# ChessMate.net
KiCad netlist of a schematic drawn in EAGLE
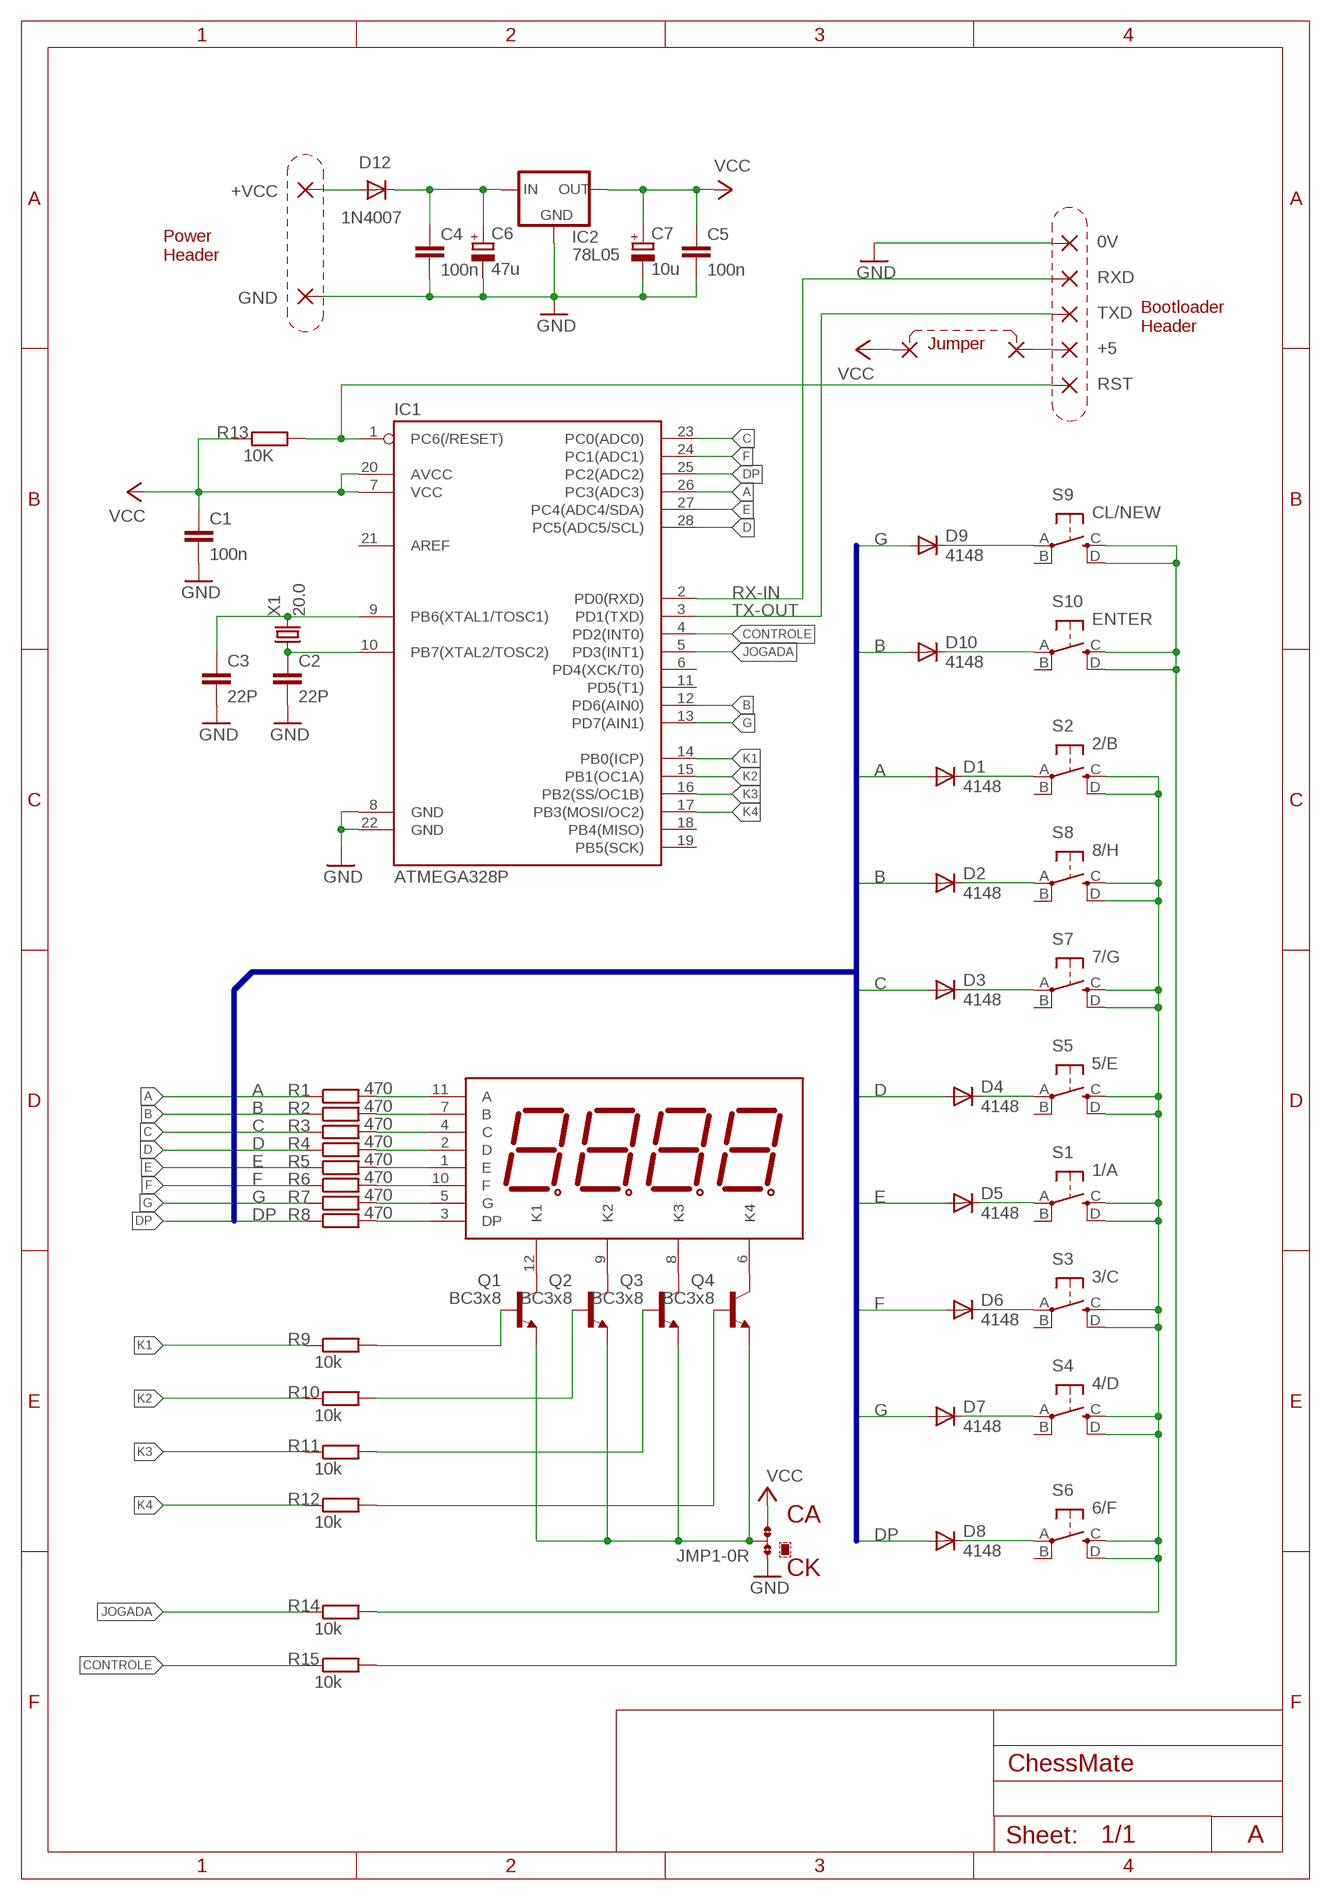
[diagram p0: schematic, sheet 1]

(export (version "E")
  (design (tool "Eeschema 10.0.6"))
  (components
    (comp (ref "+5")
      (value "2,15/1,0")
      (footprint "eagle-import:2,15_1,0")
      (libsource (lib "eagle-import") (part "2,15/1,0"))
    )
    (comp (ref "+VCC")
      (value "2,15/1,0")
      (footprint "eagle-import:2,15_1,0")
      (libsource (lib "eagle-import") (part "2,15/1,0"))
    )
    (comp (ref "0V")
      (value "2,15/1,0")
      (footprint "eagle-import:2,15_1,0")
      (libsource (lib "eagle-import") (part "2,15/1,0"))
    )
    (comp (ref "C1")
      (value "100n")
      (footprint "eagle-import:C050-024X044L")
      (libsource (lib "eagle-import") (part "C-EUC050-024X044L"))
    )
    (comp (ref "C2")
      (value "22P")
      (footprint "eagle-import:C025-024X044L")
      (libsource (lib "eagle-import") (part "C-EU"))
    )
    (comp (ref "C3")
      (value "22P")
      (footprint "eagle-import:C025-024X044L")
      (libsource (lib "eagle-import") (part "C-EU"))
    )
    (comp (ref "C4")
      (value "100n")
      (footprint "eagle-import:C050-024X044L")
      (libsource (lib "eagle-import") (part "C-EUC050-024X044L"))
    )
    (comp (ref "C5")
      (value "100n")
      (footprint "eagle-import:C050-024X044L")
      (libsource (lib "eagle-import") (part "C-EUC050-024X044L"))
    )
    (comp (ref "C6")
      (value "47u")
      (footprint "eagle-import:TT2D7L")
      (libsource (lib "eagle-import") (part "CPOL-EUTT2D7L"))
    )
    (comp (ref "C7")
      (value "10u")
      (footprint "eagle-import:TT2D7L")
      (libsource (lib "eagle-import") (part "CPOL-EUTT2D7L"))
    )
    (comp (ref "D1")
      (value "4148")
      (footprint "eagle-import:DO35-7")
      (libsource (lib "eagle-import") (part "1N4148DO35-7"))
    )
    (comp (ref "D2")
      (value "4148")
      (footprint "eagle-import:DO35-7")
      (libsource (lib "eagle-import") (part "1N4148DO35-7"))
    )
    (comp (ref "D3")
      (value "4148")
      (footprint "eagle-import:DO35-7")
      (libsource (lib "eagle-import") (part "1N4148DO35-7"))
    )
    (comp (ref "D4")
      (value "4148")
      (footprint "eagle-import:DO35-7")
      (libsource (lib "eagle-import") (part "1N4148DO35-7"))
    )
    (comp (ref "D5")
      (value "4148")
      (footprint "eagle-import:DO35-7")
      (libsource (lib "eagle-import") (part "1N4148DO35-7"))
    )
    (comp (ref "D6")
      (value "4148")
      (footprint "eagle-import:DO35-7")
      (libsource (lib "eagle-import") (part "1N4148DO35-7"))
    )
    (comp (ref "D7")
      (value "4148")
      (footprint "eagle-import:DO35-7")
      (libsource (lib "eagle-import") (part "1N4148DO35-7"))
    )
    (comp (ref "D8")
      (value "4148")
      (footprint "eagle-import:DO35-7")
      (libsource (lib "eagle-import") (part "1N4148DO35-7"))
    )
    (comp (ref "D9")
      (value "4148")
      (footprint "eagle-import:DO35-7")
      (libsource (lib "eagle-import") (part "1N4148DO35-7"))
    )
    (comp (ref "D10")
      (value "4148")
      (footprint "eagle-import:DO35-7")
      (libsource (lib "eagle-import") (part "1N4148DO35-7"))
    )
    (comp (ref "D12")
      (value "1N4007")
      (footprint "eagle-import:DO41-7.6L")
      (libsource (lib "eagle-import") (part "DIODE-DO41-7.7L"))
    )
    (comp (ref "GND")
      (value "2,15/1,0")
      (footprint "eagle-import:2,15_1,0")
      (libsource (lib "eagle-import") (part "2,15/1,0"))
    )
    (comp (ref "IC1")
      (value "ATMEGA328P")
      (footprint "eagle-import:DIL28-3")
      (libsource (lib "eagle-import") (part "ATMEGA328P_PDIP"))
    )
    (comp (ref "IC2")
      (value "78L05")
      (footprint "eagle-import:TO92_")
      (libsource (lib "eagle-import") (part "78LXXTO92_"))
    )
    (comp (ref "JMP1")
      (value "0R-JUMPA")
      (footprint "eagle-import:A0R-JMP")
      (libsource (lib "eagle-import") (part "0R-JUMPA"))
    )
    (comp (ref "LD1")
      (value "4_DIGIT-TOF3461BH-N")
      (footprint "eagle-import:TOF3461BH-N")
      (libsource (lib "eagle-import") (part "4_DIGIT-TOF3461BH-N"))
    )
    (comp (ref "PAD1")
      (value "1,6/0,8")
      (footprint "eagle-import:1,6_0,8")
      (libsource (lib "eagle-import") (part "1,6/0,8"))
    )
    (comp (ref "PAD2")
      (value "1,6/0,8")
      (footprint "eagle-import:1,6_0,8")
      (libsource (lib "eagle-import") (part "1,6/0,8"))
    )
    (comp (ref "Q1")
      (value "BC3x8")
      (footprint "eagle-import:TO92-EBC")
      (libsource (lib "eagle-import") (part "BC338"))
    )
    (comp (ref "Q2")
      (value "BC3x8")
      (footprint "eagle-import:TO92-EBC")
      (libsource (lib "eagle-import") (part "BC338"))
    )
    (comp (ref "Q3")
      (value "BC3x8")
      (footprint "eagle-import:TO92-EBC")
      (libsource (lib "eagle-import") (part "BC338"))
    )
    (comp (ref "Q4")
      (value "BC3x8")
      (footprint "eagle-import:TO92-EBC")
      (libsource (lib "eagle-import") (part "BC338"))
    )
    (comp (ref "R1")
      (value "470")
      (footprint "eagle-import:0204_7L")
      (libsource (lib "eagle-import") (part "R-EU_0204/7L"))
    )
    (comp (ref "R2")
      (value "470")
      (footprint "eagle-import:0204_7L")
      (libsource (lib "eagle-import") (part "R-EU_0204/7L"))
    )
    (comp (ref "R3")
      (value "470")
      (footprint "eagle-import:0204_7L")
      (libsource (lib "eagle-import") (part "R-EU_0204/7L"))
    )
    (comp (ref "R4")
      (value "470")
      (footprint "eagle-import:0204_7L")
      (libsource (lib "eagle-import") (part "R-EU_0204/7L"))
    )
    (comp (ref "R5")
      (value "470")
      (footprint "eagle-import:0204_7L")
      (libsource (lib "eagle-import") (part "R-EU_0204/7L"))
    )
    (comp (ref "R6")
      (value "470")
      (footprint "eagle-import:0204_7L")
      (libsource (lib "eagle-import") (part "R-EU_0204/7L"))
    )
    (comp (ref "R7")
      (value "470")
      (footprint "eagle-import:0204_7L")
      (libsource (lib "eagle-import") (part "R-EU_0204/7L"))
    )
    (comp (ref "R8")
      (value "470")
      (footprint "eagle-import:0204_7L")
      (libsource (lib "eagle-import") (part "R-EU_0204/7L"))
    )
    (comp (ref "R9")
      (value "10k")
      (footprint "eagle-import:0204_7L")
      (libsource (lib "eagle-import") (part "R-EU_0204/7L"))
    )
    (comp (ref "R10")
      (value "10k")
      (footprint "eagle-import:0204_7L")
      (libsource (lib "eagle-import") (part "R-EU_0204/7L"))
    )
    (comp (ref "R11")
      (value "10k")
      (footprint "eagle-import:0204_7L")
      (libsource (lib "eagle-import") (part "R-EU_0204/7L"))
    )
    (comp (ref "R12")
      (value "10k")
      (footprint "eagle-import:0204_7L")
      (libsource (lib "eagle-import") (part "R-EU_0204/7L"))
    )
    (comp (ref "R13")
      (value "10K")
      (footprint "eagle-import:0204_5L")
      (libsource (lib "eagle-import") (part "R-EU_0204/5L"))
    )
    (comp (ref "R14")
      (value "10k")
      (footprint "eagle-import:0204_7L")
      (libsource (lib "eagle-import") (part "R-EU_0204/7L"))
    )
    (comp (ref "R15")
      (value "10k")
      (footprint "eagle-import:0204_7L")
      (libsource (lib "eagle-import") (part "R-EU_0204/7L"))
    )
    (comp (ref "RST")
      (value "2,15/1,0")
      (footprint "eagle-import:2,15_1,0")
      (libsource (lib "eagle-import") (part "2,15/1,0"))
    )
    (comp (ref "RXD")
      (value "2,15/1,0")
      (footprint "eagle-import:2,15_1,0")
      (libsource (lib "eagle-import") (part "2,15/1,0"))
    )
    (comp (ref "S1")
      (value "1/A")
      (footprint "eagle-import:TACT_SW")
      (libsource (lib "eagle-import") (part "10-XXTACT"))
    )
    (comp (ref "S2")
      (value "2/B")
      (footprint "eagle-import:TACT_SW")
      (libsource (lib "eagle-import") (part "10-XXTACT"))
    )
    (comp (ref "S3")
      (value "3/C")
      (footprint "eagle-import:TACT_SW")
      (libsource (lib "eagle-import") (part "10-XXTACT"))
    )
    (comp (ref "S4")
      (value "4/D")
      (footprint "eagle-import:TACT_SW")
      (libsource (lib "eagle-import") (part "10-XXTACT"))
    )
    (comp (ref "S5")
      (value "5/E")
      (footprint "eagle-import:TACT_SW")
      (libsource (lib "eagle-import") (part "10-XXTACT"))
    )
    (comp (ref "S6")
      (value "6/F")
      (footprint "eagle-import:TACT_SW")
      (libsource (lib "eagle-import") (part "10-XXTACT"))
    )
    (comp (ref "S7")
      (value "7/G")
      (footprint "eagle-import:TACT_SW")
      (libsource (lib "eagle-import") (part "10-XXTACT"))
    )
    (comp (ref "S8")
      (value "8/H")
      (footprint "eagle-import:TACT_SW")
      (libsource (lib "eagle-import") (part "10-XXTACT"))
    )
    (comp (ref "S9")
      (value "CL/NEW")
      (footprint "eagle-import:TACT_SW")
      (libsource (lib "eagle-import") (part "10-XXTACT"))
    )
    (comp (ref "S10")
      (value "ENTER")
      (footprint "eagle-import:TACT_SW")
      (libsource (lib "eagle-import") (part "10-XXTACT"))
    )
    (comp (ref "TXD")
      (value "2,15/1,0")
      (footprint "eagle-import:2,15_1,0")
      (libsource (lib "eagle-import") (part "2,15/1,0"))
    )
    (comp (ref "X1")
      (value "20.0")
      (footprint "eagle-import:HC49_SL")
      (libsource (lib "eagle-import") (part "CRYSTALHC49/SL"))
    )
  )
  (nets
    (net (code "1") (name "/RX-IN") (class "Default")
      (node (ref "IC1") (pin "2") (pinfunction "PD0(RXD)_2") (pintype "bidirectional"))
      (node (ref "RXD") (pin "1") (pinfunction "P_1") (pintype "passive"))
    )
    (net (code "2") (name "/TX-OUT") (class "Default")
      (node (ref "IC1") (pin "3") (pinfunction "PD1(TXD)_3") (pintype "bidirectional"))
      (node (ref "TXD") (pin "1") (pinfunction "P_1") (pintype "passive"))
    )
    (net (code "3") (name "A") (class "Default")
      (node (ref "D1") (pin "A") (pinfunction "A_A") (pintype "passive"))
      (node (ref "IC1") (pin "26") (pinfunction "PC3(ADC3)_26") (pintype "bidirectional"))
      (node (ref "R1") (pin "1") (pinfunction "1_1") (pintype "passive"))
    )
    (net (code "4") (name "B") (class "Default")
      (node (ref "D10") (pin "A") (pinfunction "A_A") (pintype "passive"))
      (node (ref "D2") (pin "A") (pinfunction "A_A") (pintype "passive"))
      (node (ref "IC1") (pin "12") (pinfunction "PD6(AIN0)_12") (pintype "bidirectional"))
      (node (ref "R2") (pin "1") (pinfunction "1_1") (pintype "passive"))
    )
    (net (code "5") (name "C") (class "Default")
      (node (ref "D3") (pin "A") (pinfunction "A_A") (pintype "passive"))
      (node (ref "IC1") (pin "23") (pinfunction "PC0(ADC0)_23") (pintype "bidirectional"))
      (node (ref "R3") (pin "1") (pinfunction "1_1") (pintype "passive"))
    )
    (net (code "6") (name "CONTROLE") (class "Default")
      (node (ref "IC1") (pin "4") (pinfunction "PD2(INT0)_4") (pintype "bidirectional"))
      (node (ref "R15") (pin "1") (pinfunction "1_1") (pintype "passive"))
    )
    (net (code "7") (name "D") (class "Default")
      (node (ref "D4") (pin "A") (pinfunction "A_A") (pintype "passive"))
      (node (ref "IC1") (pin "28") (pinfunction "PC5(ADC5/SCL)_28") (pintype "bidirectional"))
      (node (ref "R4") (pin "1") (pinfunction "1_1") (pintype "passive"))
    )
    (net (code "8") (name "DP") (class "Default")
      (node (ref "D8") (pin "A") (pinfunction "A_A") (pintype "passive"))
      (node (ref "IC1") (pin "25") (pinfunction "PC2(ADC2)_25") (pintype "bidirectional"))
      (node (ref "R8") (pin "1") (pinfunction "1_1") (pintype "passive"))
    )
    (net (code "9") (name "E") (class "Default")
      (node (ref "D5") (pin "A") (pinfunction "A_A") (pintype "passive"))
      (node (ref "IC1") (pin "27") (pinfunction "PC4(ADC4/SDA)_27") (pintype "bidirectional"))
      (node (ref "R5") (pin "1") (pinfunction "1_1") (pintype "passive"))
    )
    (net (code "10") (name "F") (class "Default")
      (node (ref "D6") (pin "A") (pinfunction "A_A") (pintype "passive"))
      (node (ref "IC1") (pin "24") (pinfunction "PC1(ADC1)_24") (pintype "bidirectional"))
      (node (ref "R6") (pin "1") (pinfunction "1_1") (pintype "passive"))
    )
    (net (code "11") (name "G") (class "Default")
      (node (ref "D7") (pin "A") (pinfunction "A_A") (pintype "passive"))
      (node (ref "D9") (pin "A") (pinfunction "A_A") (pintype "passive"))
      (node (ref "IC1") (pin "13") (pinfunction "PD7(AIN1)_13") (pintype "bidirectional"))
      (node (ref "R7") (pin "1") (pinfunction "1_1") (pintype "passive"))
    )
    (net (code "12") (name "GND") (class "Default")
      (node (ref "0V") (pin "1") (pinfunction "P_1") (pintype "passive"))
      (node (ref "C1") (pin "2") (pinfunction "2_2") (pintype "passive"))
      (node (ref "C2") (pin "2") (pinfunction "2_2") (pintype "passive"))
      (node (ref "C3") (pin "2") (pinfunction "2_2") (pintype "passive"))
      (node (ref "C4") (pin "2") (pinfunction "2_2") (pintype "passive"))
      (node (ref "C5") (pin "2") (pinfunction "2_2") (pintype "passive"))
      (node (ref "C6") (pin "-") (pinfunction "-_-") (pintype "passive"))
      (node (ref "C7") (pin "-") (pinfunction "-_-") (pintype "passive"))
      (node (ref "GND") (pin "1") (pinfunction "P_1") (pintype "passive"))
      (node (ref "IC1") (pin "22") (pinfunction "GND_22") (pintype "bidirectional"))
      (node (ref "IC1") (pin "8") (pinfunction "GND_8") (pintype "bidirectional"))
      (node (ref "IC2") (pin "2") (pinfunction "GND_2") (pintype "input"))
      (node (ref "JMP1") (pin "1") (pinfunction "1_1") (pintype "passive"))
    )
    (net (code "13") (name "JOGADA") (class "Default")
      (node (ref "IC1") (pin "5") (pinfunction "PD3(INT1)_5") (pintype "bidirectional"))
      (node (ref "R14") (pin "1") (pinfunction "1_1") (pintype "passive"))
    )
    (net (code "14") (name "K1") (class "Default")
      (node (ref "IC1") (pin "14") (pinfunction "PB0(ICP)_14") (pintype "bidirectional"))
      (node (ref "R9") (pin "1") (pinfunction "1_1") (pintype "passive"))
    )
    (net (code "15") (name "K2") (class "Default")
      (node (ref "IC1") (pin "15") (pinfunction "PB1(OC1A)_15") (pintype "bidirectional"))
      (node (ref "R10") (pin "1") (pinfunction "1_1") (pintype "passive"))
    )
    (net (code "16") (name "K3") (class "Default")
      (node (ref "IC1") (pin "16") (pinfunction "PB2(SS/OC1B)_16") (pintype "bidirectional"))
      (node (ref "R11") (pin "1") (pinfunction "1_1") (pintype "passive"))
    )
    (net (code "17") (name "K4") (class "Default")
      (node (ref "IC1") (pin "17") (pinfunction "PB3(MOSI/OC2)_17") (pintype "bidirectional"))
      (node (ref "R12") (pin "1") (pinfunction "1_1") (pintype "passive"))
    )
    (net (code "18") (name "Net-(+5-P)") (class "Default")
      (node (ref "+5") (pin "1") (pinfunction "P_1") (pintype "passive"))
      (node (ref "PAD2") (pin "1") (pinfunction "P_1") (pintype "passive"))
    )
    (net (code "19") (name "Net-(+VCC-P)") (class "Default")
      (node (ref "+VCC") (pin "1") (pinfunction "P_1") (pintype "passive"))
      (node (ref "D12") (pin "A") (pinfunction "A_A") (pintype "passive"))
    )
    (net (code "20") (name "Net-(IC1-PB6(XTAL1{slash}TOSC1))") (class "Default")
      (node (ref "C3") (pin "1") (pinfunction "1_1") (pintype "passive"))
      (node (ref "IC1") (pin "9") (pinfunction "PB6(XTAL1/TOSC1)_9") (pintype "bidirectional"))
      (node (ref "X1") (pin "2") (pinfunction "2_2") (pintype "passive"))
    )
    (net (code "21") (name "Net-(IC1-PB7(XTAL2{slash}TOSC2))") (class "Default")
      (node (ref "C2") (pin "1") (pinfunction "1_1") (pintype "passive"))
      (node (ref "IC1") (pin "10") (pinfunction "PB7(XTAL2/TOSC2)_10") (pintype "bidirectional"))
      (node (ref "X1") (pin "1") (pinfunction "1_1") (pintype "passive"))
    )
    (net (code "22") (name "Net-(IC1-PC6({slash}RESET))") (class "Default")
      (node (ref "IC1") (pin "1") (pinfunction "PC6(/RESET)_1") (pintype "bidirectional"))
      (node (ref "R13") (pin "2") (pinfunction "2_2") (pintype "passive"))
      (node (ref "RST") (pin "1") (pinfunction "P_1") (pintype "passive"))
    )
    (net (code "23") (name "Net-(IC2-IN)") (class "Default")
      (node (ref "C4") (pin "1") (pinfunction "1_1") (pintype "passive"))
      (node (ref "C6") (pin "+") (pinfunction "+_+") (pintype "passive"))
      (node (ref "D12") (pin "C") (pinfunction "C_C") (pintype "passive"))
      (node (ref "IC2") (pin "3") (pinfunction "IN_3") (pintype "input"))
    )
    (net (code "24") (name "Net-(JMP1-Pad2)") (class "Default")
      (node (ref "JMP1") (pin "2") (pinfunction "2_2") (pintype "passive"))
      (node (ref "Q1") (pin "E") (pinfunction "E_E") (pintype "passive"))
      (node (ref "Q2") (pin "E") (pinfunction "E_E") (pintype "passive"))
      (node (ref "Q3") (pin "E") (pinfunction "E_E") (pintype "passive"))
      (node (ref "Q4") (pin "E") (pinfunction "E_E") (pintype "passive"))
    )
    (net (code "25") (name "Net-(LD1-A)") (class "Default")
      (node (ref "LD1") (pin "11") (pinfunction "A_11") (pintype "input"))
      (node (ref "R1") (pin "2") (pinfunction "2_2") (pintype "passive"))
    )
    (net (code "26") (name "Net-(LD1-B)") (class "Default")
      (node (ref "LD1") (pin "7") (pinfunction "B_7") (pintype "input"))
      (node (ref "R2") (pin "2") (pinfunction "2_2") (pintype "passive"))
    )
    (net (code "27") (name "Net-(LD1-C)") (class "Default")
      (node (ref "LD1") (pin "4") (pinfunction "C_4") (pintype "input"))
      (node (ref "R3") (pin "2") (pinfunction "2_2") (pintype "passive"))
    )
    (net (code "28") (name "Net-(LD1-D)") (class "Default")
      (node (ref "LD1") (pin "2") (pinfunction "D_2") (pintype "input"))
      (node (ref "R4") (pin "2") (pinfunction "2_2") (pintype "passive"))
    )
    (net (code "29") (name "Net-(LD1-DP)") (class "Default")
      (node (ref "LD1") (pin "3") (pinfunction "DP_3") (pintype "input"))
      (node (ref "R8") (pin "2") (pinfunction "2_2") (pintype "passive"))
    )
    (net (code "30") (name "Net-(LD1-E)") (class "Default")
      (node (ref "LD1") (pin "1") (pinfunction "E_1") (pintype "input"))
      (node (ref "R5") (pin "2") (pinfunction "2_2") (pintype "passive"))
    )
    (net (code "31") (name "Net-(LD1-F)") (class "Default")
      (node (ref "LD1") (pin "10") (pinfunction "F_10") (pintype "input"))
      (node (ref "R6") (pin "2") (pinfunction "2_2") (pintype "passive"))
    )
    (net (code "32") (name "Net-(LD1-G)") (class "Default")
      (node (ref "LD1") (pin "5") (pinfunction "G_5") (pintype "input"))
      (node (ref "R7") (pin "2") (pinfunction "2_2") (pintype "passive"))
    )
    (net (code "33") (name "Net-(LD1-K1)") (class "Default")
      (node (ref "LD1") (pin "12") (pinfunction "K1_12") (pintype "input"))
      (node (ref "Q1") (pin "C") (pinfunction "C_C") (pintype "passive"))
    )
    (net (code "34") (name "Net-(LD1-K2)") (class "Default")
      (node (ref "LD1") (pin "9") (pinfunction "K2_9") (pintype "input"))
      (node (ref "Q2") (pin "C") (pinfunction "C_C") (pintype "passive"))
    )
    (net (code "35") (name "Net-(LD1-K3)") (class "Default")
      (node (ref "LD1") (pin "8") (pinfunction "K3_8") (pintype "input"))
      (node (ref "Q3") (pin "C") (pinfunction "C_C") (pintype "passive"))
    )
    (net (code "36") (name "Net-(LD1-K4)") (class "Default")
      (node (ref "LD1") (pin "6") (pinfunction "K4_6") (pintype "input"))
      (node (ref "Q4") (pin "C") (pinfunction "C_C") (pintype "passive"))
    )
    (net (code "37") (name "Net-(Q1-PadB)") (class "Default")
      (node (ref "Q1") (pin "B") (pinfunction "B_B") (pintype "passive"))
      (node (ref "R9") (pin "2") (pinfunction "2_2") (pintype "passive"))
    )
    (net (code "38") (name "Net-(Q2-PadB)") (class "Default")
      (node (ref "Q2") (pin "B") (pinfunction "B_B") (pintype "passive"))
      (node (ref "R10") (pin "2") (pinfunction "2_2") (pintype "passive"))
    )
    (net (code "39") (name "Net-(Q3-PadB)") (class "Default")
      (node (ref "Q3") (pin "B") (pinfunction "B_B") (pintype "passive"))
      (node (ref "R11") (pin "2") (pinfunction "2_2") (pintype "passive"))
    )
    (net (code "40") (name "Net-(Q4-PadB)") (class "Default")
      (node (ref "Q4") (pin "B") (pinfunction "B_B") (pintype "passive"))
      (node (ref "R12") (pin "2") (pinfunction "2_2") (pintype "passive"))
    )
    (net (code "41") (name "Net-(S1-P)") (class "Default")
      (node (ref "D5") (pin "C") (pinfunction "C_C") (pintype "passive"))
      (node (ref "S1") (pin "A") (pinfunction "P_A") (pintype "passive"))
    )
    (net (code "42") (name "Net-(S1-S)") (class "Default")
      (node (ref "R14") (pin "2") (pinfunction "2_2") (pintype "passive"))
      (node (ref "S1") (pin "C") (pinfunction "S_C") (pintype "passive"))
      (node (ref "S1") (pin "D") (pinfunction "S1_D") (pintype "passive"))
      (node (ref "S2") (pin "C") (pinfunction "S_C") (pintype "passive"))
      (node (ref "S2") (pin "D") (pinfunction "S1_D") (pintype "passive"))
      (node (ref "S3") (pin "C") (pinfunction "S_C") (pintype "passive"))
      (node (ref "S3") (pin "D") (pinfunction "S1_D") (pintype "passive"))
      (node (ref "S4") (pin "C") (pinfunction "S_C") (pintype "passive"))
      (node (ref "S4") (pin "D") (pinfunction "S1_D") (pintype "passive"))
      (node (ref "S5") (pin "C") (pinfunction "S_C") (pintype "passive"))
      (node (ref "S5") (pin "D") (pinfunction "S1_D") (pintype "passive"))
      (node (ref "S6") (pin "C") (pinfunction "S_C") (pintype "passive"))
      (node (ref "S6") (pin "D") (pinfunction "S1_D") (pintype "passive"))
      (node (ref "S7") (pin "C") (pinfunction "S_C") (pintype "passive"))
      (node (ref "S7") (pin "D") (pinfunction "S1_D") (pintype "passive"))
      (node (ref "S8") (pin "C") (pinfunction "S_C") (pintype "passive"))
      (node (ref "S8") (pin "D") (pinfunction "S1_D") (pintype "passive"))
    )
    (net (code "43") (name "Net-(S2-P)") (class "Default")
      (node (ref "D1") (pin "C") (pinfunction "C_C") (pintype "passive"))
      (node (ref "S2") (pin "A") (pinfunction "P_A") (pintype "passive"))
    )
    (net (code "44") (name "Net-(S3-P)") (class "Default")
      (node (ref "D6") (pin "C") (pinfunction "C_C") (pintype "passive"))
      (node (ref "S3") (pin "A") (pinfunction "P_A") (pintype "passive"))
    )
    (net (code "45") (name "Net-(S4-P)") (class "Default")
      (node (ref "D7") (pin "C") (pinfunction "C_C") (pintype "passive"))
      (node (ref "S4") (pin "A") (pinfunction "P_A") (pintype "passive"))
    )
    (net (code "46") (name "Net-(S5-P)") (class "Default")
      (node (ref "D4") (pin "C") (pinfunction "C_C") (pintype "passive"))
      (node (ref "S5") (pin "A") (pinfunction "P_A") (pintype "passive"))
    )
    (net (code "47") (name "Net-(S6-P)") (class "Default")
      (node (ref "D8") (pin "C") (pinfunction "C_C") (pintype "passive"))
      (node (ref "S6") (pin "A") (pinfunction "P_A") (pintype "passive"))
    )
    (net (code "48") (name "Net-(S7-P)") (class "Default")
      (node (ref "D3") (pin "C") (pinfunction "C_C") (pintype "passive"))
      (node (ref "S7") (pin "A") (pinfunction "P_A") (pintype "passive"))
    )
    (net (code "49") (name "Net-(S8-P)") (class "Default")
      (node (ref "D2") (pin "C") (pinfunction "C_C") (pintype "passive"))
      (node (ref "S8") (pin "A") (pinfunction "P_A") (pintype "passive"))
    )
    (net (code "50") (name "Net-(S9-P)") (class "Default")
      (node (ref "D9") (pin "C") (pinfunction "C_C") (pintype "passive"))
      (node (ref "S9") (pin "A") (pinfunction "P_A") (pintype "passive"))
    )
    (net (code "51") (name "Net-(S10-P)") (class "Default")
      (node (ref "D10") (pin "C") (pinfunction "C_C") (pintype "passive"))
      (node (ref "S10") (pin "A") (pinfunction "P_A") (pintype "passive"))
    )
    (net (code "52") (name "Net-(S10-S)") (class "Default")
      (node (ref "R15") (pin "2") (pinfunction "2_2") (pintype "passive"))
      (node (ref "S10") (pin "C") (pinfunction "S_C") (pintype "passive"))
      (node (ref "S10") (pin "D") (pinfunction "S1_D") (pintype "passive"))
      (node (ref "S9") (pin "C") (pinfunction "S_C") (pintype "passive"))
      (node (ref "S9") (pin "D") (pinfunction "S1_D") (pintype "passive"))
    )
    (net (code "53") (name "VCC") (class "Default")
      (node (ref "C1") (pin "1") (pinfunction "1_1") (pintype "passive"))
      (node (ref "C5") (pin "1") (pinfunction "1_1") (pintype "passive"))
      (node (ref "C7") (pin "+") (pinfunction "+_+") (pintype "passive"))
      (node (ref "IC1") (pin "20") (pinfunction "AVCC_20") (pintype "bidirectional"))
      (node (ref "IC1") (pin "7") (pinfunction "VCC_7") (pintype "bidirectional"))
      (node (ref "IC2") (pin "1") (pinfunction "OUT_1") (pintype "passive"))
      (node (ref "JMP1") (pin "3") (pinfunction "3_3") (pintype "passive"))
      (node (ref "PAD1") (pin "1") (pinfunction "P_1") (pintype "passive"))
      (node (ref "R13") (pin "1") (pinfunction "1_1") (pintype "passive"))
    )
    (net (code "54") (name "unconnected-(IC1-AREF-Pad21)") (class "Default")
      (node (ref "IC1") (pin "21") (pinfunction "AREF_21") (pintype "bidirectional"))
    )
    (net (code "55") (name "unconnected-(IC1-PB4(MISO)-Pad18)") (class "Default")
      (node (ref "IC1") (pin "18") (pinfunction "PB4(MISO)_18") (pintype "bidirectional"))
    )
    (net (code "56") (name "unconnected-(IC1-PB5(SCK)-Pad19)") (class "Default")
      (node (ref "IC1") (pin "19") (pinfunction "PB5(SCK)_19") (pintype "bidirectional"))
    )
    (net (code "57") (name "unconnected-(IC1-PD4(XCK{slash}T0)-Pad6)") (class "Default")
      (node (ref "IC1") (pin "6") (pinfunction "PD4(XCK/T0)_6") (pintype "bidirectional"))
    )
    (net (code "58") (name "unconnected-(IC1-PD5(T1)-Pad11)") (class "Default")
      (node (ref "IC1") (pin "11") (pinfunction "PD5(T1)_11") (pintype "bidirectional"))
    )
    (net (code "59") (name "unconnected-(S1-P1-PadB)") (class "Default")
      (node (ref "S1") (pin "B") (pinfunction "P1_B") (pintype "passive"))
    )
    (net (code "60") (name "unconnected-(S2-P1-PadB)") (class "Default")
      (node (ref "S2") (pin "B") (pinfunction "P1_B") (pintype "passive"))
    )
    (net (code "61") (name "unconnected-(S3-P1-PadB)") (class "Default")
      (node (ref "S3") (pin "B") (pinfunction "P1_B") (pintype "passive"))
    )
    (net (code "62") (name "unconnected-(S4-P1-PadB)") (class "Default")
      (node (ref "S4") (pin "B") (pinfunction "P1_B") (pintype "passive"))
    )
    (net (code "63") (name "unconnected-(S5-P1-PadB)") (class "Default")
      (node (ref "S5") (pin "B") (pinfunction "P1_B") (pintype "passive"))
    )
    (net (code "64") (name "unconnected-(S6-P1-PadB)") (class "Default")
      (node (ref "S6") (pin "B") (pinfunction "P1_B") (pintype "passive"))
    )
    (net (code "65") (name "unconnected-(S7-P1-PadB)") (class "Default")
      (node (ref "S7") (pin "B") (pinfunction "P1_B") (pintype "passive"))
    )
    (net (code "66") (name "unconnected-(S8-P1-PadB)") (class "Default")
      (node (ref "S8") (pin "B") (pinfunction "P1_B") (pintype "passive"))
    )
    (net (code "67") (name "unconnected-(S9-P1-PadB)") (class "Default")
      (node (ref "S9") (pin "B") (pinfunction "P1_B") (pintype "passive"))
    )
    (net (code "68") (name "unconnected-(S10-P1-PadB)") (class "Default")
      (node (ref "S10") (pin "B") (pinfunction "P1_B") (pintype "passive"))
    )
  )
)
